# Portaqua.net
KiCad netlist of a schematic drawn in EAGLE
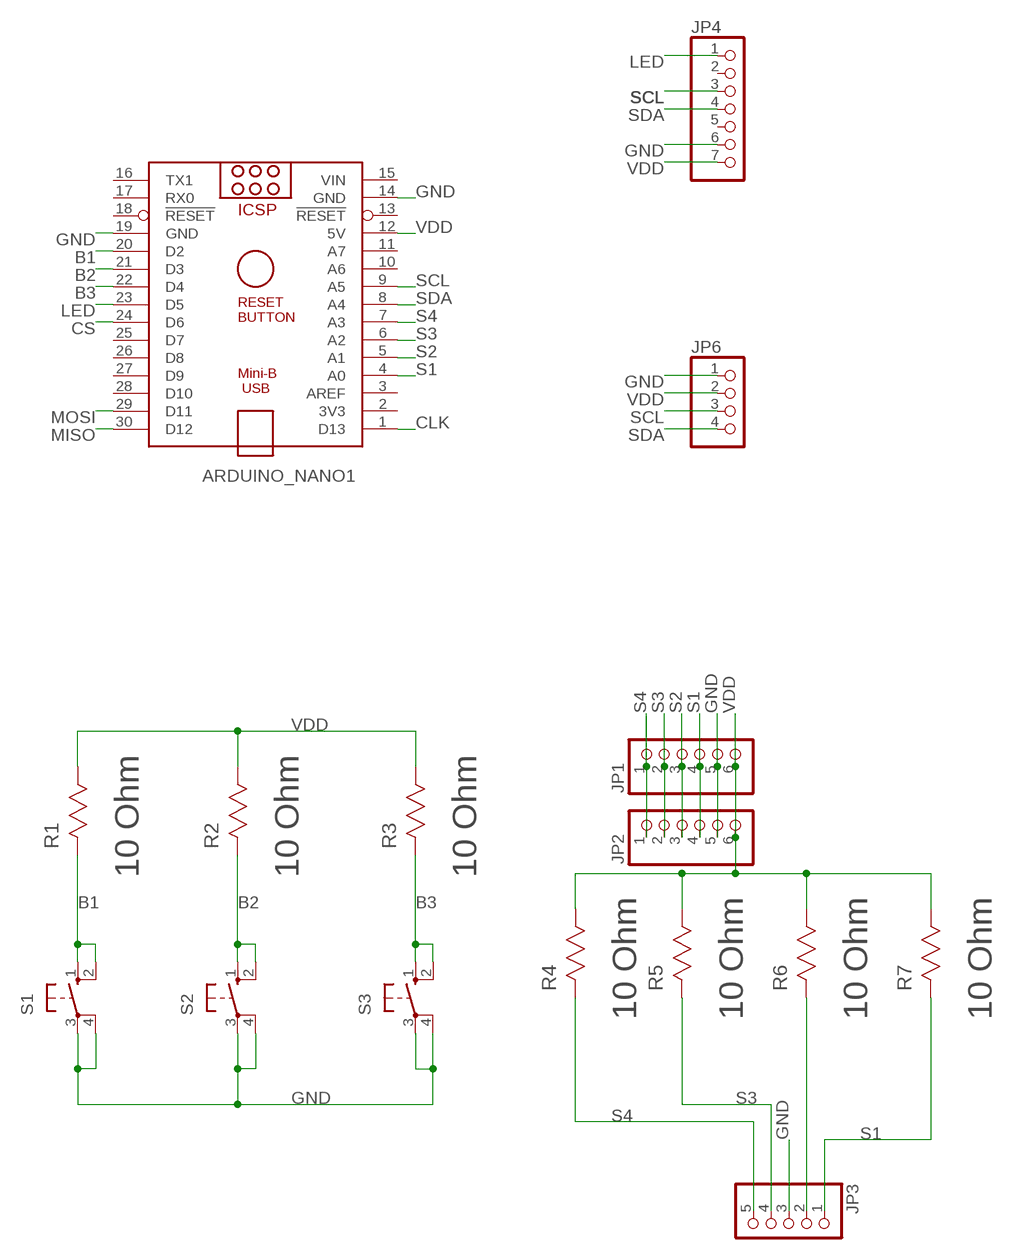
[diagram p0: schematic, sheet 1]

(export (version "E")
  (design (tool "Eeschema 10.0.6"))
  (components
    (comp (ref "ARDUINO_NANO1")
      (value "ARDUINO_NANO")
      (footprint "eagle-import:ARDUINO_NANO")
      (libsource (lib "eagle-import") (part "ARDUINO_NANO"))
    )
    (comp (ref "JP1")
      (value "PINHD-1X6")
      (footprint "eagle-import:1X06")
      (libsource (lib "eagle-import") (part "PINHD-1X6"))
    )
    (comp (ref "JP2")
      (value "PINHD-1X6")
      (footprint "eagle-import:1X06")
      (libsource (lib "eagle-import") (part "PINHD-1X6"))
    )
    (comp (ref "JP3")
      (value "PINHD-1X05_2.54-SMD-90°")
      (footprint "eagle-import:1X05SMD_90")
      (libsource (lib "eagle-import") (part "PINHD-1X05_2.54-SMD-90°"))
    )
    (comp (ref "JP4")
      (value "PINHD-1X7")
      (footprint "eagle-import:1X07")
      (libsource (lib "eagle-import") (part "PINHD-1X7"))
    )
    (comp (ref "JP6")
      (value "PINHD-1X4")
      (footprint "eagle-import:1X04")
      (libsource (lib "eagle-import") (part "PINHD-1X4"))
    )
    (comp (ref "R1")
      (value "10 Ohm")
      (footprint "eagle-import:RESC3216X71N")
      (fields (field (name "MPN") "CRM1206-FX-10R0ELF") (field (name "TOLERANCE") "±1 %"))
      (libsource (lib "eagle-import") (part "CRM1206-FX-10R0ELF"))
    )
    (comp (ref "R2")
      (value "10 Ohm")
      (footprint "eagle-import:RESC3216X71N")
      (fields (field (name "MPN") "CRM1206-FX-10R0ELF") (field (name "TOLERANCE") "±1 %"))
      (libsource (lib "eagle-import") (part "CRM1206-FX-10R0ELF"))
    )
    (comp (ref "R3")
      (value "10 Ohm")
      (footprint "eagle-import:RESC3216X71N")
      (fields (field (name "MPN") "CRM1206-FX-10R0ELF") (field (name "TOLERANCE") "±1 %"))
      (libsource (lib "eagle-import") (part "CRM1206-FX-10R0ELF"))
    )
    (comp (ref "R4")
      (value "10 Ohm")
      (footprint "eagle-import:RESC3216X71N")
      (fields (field (name "MPN") "CRM1206-FX-10R0ELF") (field (name "TOLERANCE") "±1 %"))
      (libsource (lib "eagle-import") (part "CRM1206-FX-10R0ELF"))
    )
    (comp (ref "R5")
      (value "10 Ohm")
      (footprint "eagle-import:RESC3216X71N")
      (fields (field (name "MPN") "CRM1206-FX-10R0ELF") (field (name "TOLERANCE") "±1 %"))
      (libsource (lib "eagle-import") (part "CRM1206-FX-10R0ELF"))
    )
    (comp (ref "R6")
      (value "10 Ohm")
      (footprint "eagle-import:RESC3216X71N")
      (fields (field (name "MPN") "CRM1206-FX-10R0ELF") (field (name "TOLERANCE") "±1 %"))
      (libsource (lib "eagle-import") (part "CRM1206-FX-10R0ELF"))
    )
    (comp (ref "R7")
      (value "10 Ohm")
      (footprint "eagle-import:RESC3216X71N")
      (fields (field (name "MPN") "CRM1206-FX-10R0ELF") (field (name "TOLERANCE") "±1 %"))
      (libsource (lib "eagle-import") (part "CRM1206-FX-10R0ELF"))
    )
    (comp (ref "S1")
      (value "10-XX")
      (footprint "eagle-import:B3F-10XX")
      (fields (field (name "MPN") "B3F-1000"))
      (libsource (lib "eagle-import") (part "10-XX"))
    )
    (comp (ref "S2")
      (value "10-XX")
      (footprint "eagle-import:B3F-10XX")
      (fields (field (name "MPN") "B3F-1000"))
      (libsource (lib "eagle-import") (part "10-XX"))
    )
    (comp (ref "S3")
      (value "10-XX")
      (footprint "eagle-import:B3F-10XX")
      (fields (field (name "MPN") "B3F-1000"))
      (libsource (lib "eagle-import") (part "10-XX"))
    )
  )
  (nets
    (net (code "1") (name "/B1") (class "Default")
      (node (ref "ARDUINO_NANO1") (pin "20") (pinfunction "D2_20") (pintype "bidirectional"))
      (node (ref "R1") (pin "2") (pinfunction "R2_2") (pintype "passive"))
      (node (ref "S1") (pin "1") (pinfunction "S_1") (pintype "passive"))
      (node (ref "S1") (pin "2") (pinfunction "S1_2") (pintype "passive"))
    )
    (net (code "2") (name "/B2") (class "Default")
      (node (ref "ARDUINO_NANO1") (pin "21") (pinfunction "D3_21") (pintype "bidirectional"))
      (node (ref "R2") (pin "2") (pinfunction "R2_2") (pintype "passive"))
      (node (ref "S2") (pin "1") (pinfunction "S_1") (pintype "passive"))
      (node (ref "S2") (pin "2") (pinfunction "S1_2") (pintype "passive"))
    )
    (net (code "3") (name "/B3") (class "Default")
      (node (ref "ARDUINO_NANO1") (pin "22") (pinfunction "D4_22") (pintype "bidirectional"))
      (node (ref "R3") (pin "2") (pinfunction "R2_2") (pintype "passive"))
      (node (ref "S3") (pin "1") (pinfunction "S_1") (pintype "passive"))
      (node (ref "S3") (pin "2") (pinfunction "S1_2") (pintype "passive"))
    )
    (net (code "4") (name "/CLK") (class "Default")
      (node (ref "ARDUINO_NANO1") (pin "1") (pinfunction "D13_1") (pintype "bidirectional"))
    )
    (net (code "5") (name "/CS") (class "Default")
      (node (ref "ARDUINO_NANO1") (pin "24") (pinfunction "D6_24") (pintype "bidirectional"))
    )
    (net (code "6") (name "/GND") (class "Default")
      (node (ref "ARDUINO_NANO1") (pin "14") (pinfunction "GND_14") (pintype "power_in"))
      (node (ref "ARDUINO_NANO1") (pin "19") (pinfunction "GND_19") (pintype "power_in"))
      (node (ref "JP1") (pin "5") (pinfunction "5_5") (pintype "passive"))
      (node (ref "JP2") (pin "5") (pinfunction "5_5") (pintype "passive"))
      (node (ref "JP3") (pin "3") (pinfunction "3_3") (pintype "passive"))
      (node (ref "JP4") (pin "6") (pinfunction "6_6") (pintype "passive"))
      (node (ref "JP6") (pin "1") (pinfunction "1_1") (pintype "passive"))
      (node (ref "S1") (pin "3") (pinfunction "P_3") (pintype "passive"))
      (node (ref "S1") (pin "4") (pinfunction "P1_4") (pintype "passive"))
      (node (ref "S2") (pin "3") (pinfunction "P_3") (pintype "passive"))
      (node (ref "S2") (pin "4") (pinfunction "P1_4") (pintype "passive"))
      (node (ref "S3") (pin "3") (pinfunction "P_3") (pintype "passive"))
      (node (ref "S3") (pin "4") (pinfunction "P1_4") (pintype "passive"))
    )
    (net (code "7") (name "/LED") (class "Default")
      (node (ref "ARDUINO_NANO1") (pin "23") (pinfunction "D5_23") (pintype "bidirectional"))
      (node (ref "JP4") (pin "1") (pinfunction "1_1") (pintype "passive"))
    )
    (net (code "8") (name "/MISO") (class "Default")
      (node (ref "ARDUINO_NANO1") (pin "30") (pinfunction "D12_30") (pintype "bidirectional"))
    )
    (net (code "9") (name "/MOSI") (class "Default")
      (node (ref "ARDUINO_NANO1") (pin "29") (pinfunction "D11_29") (pintype "bidirectional"))
    )
    (net (code "10") (name "/S1") (class "Default")
      (node (ref "ARDUINO_NANO1") (pin "4") (pinfunction "A0_4") (pintype "bidirectional"))
      (node (ref "JP1") (pin "4") (pinfunction "4_4") (pintype "passive"))
      (node (ref "JP2") (pin "4") (pinfunction "4_4") (pintype "passive"))
      (node (ref "JP3") (pin "1") (pinfunction "1_1") (pintype "passive"))
      (node (ref "R7") (pin "2") (pinfunction "R2_2") (pintype "passive"))
    )
    (net (code "11") (name "/S2") (class "Default")
      (node (ref "ARDUINO_NANO1") (pin "5") (pinfunction "A1_5") (pintype "bidirectional"))
      (node (ref "JP1") (pin "3") (pinfunction "3_3") (pintype "passive"))
      (node (ref "JP2") (pin "3") (pinfunction "3_3") (pintype "passive"))
    )
    (net (code "12") (name "/S3") (class "Default")
      (node (ref "ARDUINO_NANO1") (pin "6") (pinfunction "A2_6") (pintype "bidirectional"))
      (node (ref "JP1") (pin "2") (pinfunction "2_2") (pintype "passive"))
      (node (ref "JP2") (pin "2") (pinfunction "2_2") (pintype "passive"))
      (node (ref "JP3") (pin "4") (pinfunction "4_4") (pintype "passive"))
      (node (ref "R5") (pin "2") (pinfunction "R2_2") (pintype "passive"))
    )
    (net (code "13") (name "/S4") (class "Default")
      (node (ref "ARDUINO_NANO1") (pin "7") (pinfunction "A3_7") (pintype "bidirectional"))
      (node (ref "JP1") (pin "1") (pinfunction "1_1") (pintype "passive"))
      (node (ref "JP2") (pin "1") (pinfunction "1_1") (pintype "passive"))
      (node (ref "JP3") (pin "5") (pinfunction "5_5") (pintype "passive"))
      (node (ref "R4") (pin "2") (pinfunction "R2_2") (pintype "passive"))
    )
    (net (code "14") (name "/SCL") (class "Default")
      (node (ref "ARDUINO_NANO1") (pin "9") (pinfunction "A5_9") (pintype "bidirectional"))
      (node (ref "JP4") (pin "3") (pinfunction "3_3") (pintype "passive"))
      (node (ref "JP6") (pin "3") (pinfunction "3_3") (pintype "passive"))
    )
    (net (code "15") (name "/SDA") (class "Default")
      (node (ref "ARDUINO_NANO1") (pin "8") (pinfunction "A4_8") (pintype "bidirectional"))
      (node (ref "JP4") (pin "4") (pinfunction "4_4") (pintype "passive"))
      (node (ref "JP6") (pin "4") (pinfunction "4_4") (pintype "passive"))
    )
    (net (code "16") (name "/VDD") (class "Default")
      (node (ref "ARDUINO_NANO1") (pin "12") (pinfunction "5V_12") (pintype "power_in"))
      (node (ref "JP1") (pin "6") (pinfunction "6_6") (pintype "passive"))
      (node (ref "JP2") (pin "6") (pinfunction "6_6") (pintype "passive"))
      (node (ref "JP4") (pin "7") (pinfunction "7_7") (pintype "passive"))
      (node (ref "JP6") (pin "2") (pinfunction "2_2") (pintype "passive"))
      (node (ref "R1") (pin "1") (pinfunction "R1_1") (pintype "passive"))
      (node (ref "R2") (pin "1") (pinfunction "R1_1") (pintype "passive"))
      (node (ref "R3") (pin "1") (pinfunction "R1_1") (pintype "passive"))
      (node (ref "R4") (pin "1") (pinfunction "R1_1") (pintype "passive"))
      (node (ref "R5") (pin "1") (pinfunction "R1_1") (pintype "passive"))
      (node (ref "R6") (pin "1") (pinfunction "R1_1") (pintype "passive"))
      (node (ref "R7") (pin "1") (pinfunction "R1_1") (pintype "passive"))
    )
    (net (code "17") (name "/VIN") (class "Default")
      (node (ref "ARDUINO_NANO1") (pin "15") (pinfunction "VIN_15") (pintype "power_in"))
    )
    (net (code "18") (name "Net-(R6-R2)") (class "Default")
      (node (ref "JP3") (pin "2") (pinfunction "2_2") (pintype "passive"))
      (node (ref "R6") (pin "2") (pinfunction "R2_2") (pintype "passive"))
    )
    (net (code "19") (name "unconnected-(ARDUINO_NANO1-3V3-Pad2)") (class "Default")
      (node (ref "ARDUINO_NANO1") (pin "2") (pinfunction "3V3_2") (pintype "output"))
    )
    (net (code "20") (name "unconnected-(ARDUINO_NANO1-A6-Pad10)") (class "Default")
      (node (ref "ARDUINO_NANO1") (pin "10") (pinfunction "A6_10") (pintype "bidirectional"))
    )
    (net (code "21") (name "unconnected-(ARDUINO_NANO1-A7-Pad11)") (class "Default")
      (node (ref "ARDUINO_NANO1") (pin "11") (pinfunction "A7_11") (pintype "bidirectional"))
    )
    (net (code "22") (name "unconnected-(ARDUINO_NANO1-AREF-Pad3)") (class "Default")
      (node (ref "ARDUINO_NANO1") (pin "3") (pinfunction "AREF_3") (pintype "input"))
    )
    (net (code "23") (name "unconnected-(ARDUINO_NANO1-D7-Pad25)") (class "Default")
      (node (ref "ARDUINO_NANO1") (pin "25") (pinfunction "D7_25") (pintype "bidirectional"))
    )
    (net (code "24") (name "unconnected-(ARDUINO_NANO1-D8-Pad26)") (class "Default")
      (node (ref "ARDUINO_NANO1") (pin "26") (pinfunction "D8_26") (pintype "bidirectional"))
    )
    (net (code "25") (name "unconnected-(ARDUINO_NANO1-D9-Pad27)") (class "Default")
      (node (ref "ARDUINO_NANO1") (pin "27") (pinfunction "D9_27") (pintype "bidirectional"))
    )
    (net (code "26") (name "unconnected-(ARDUINO_NANO1-D10-Pad28)") (class "Default")
      (node (ref "ARDUINO_NANO1") (pin "28") (pinfunction "D10_28") (pintype "bidirectional"))
    )
    (net (code "27") (name "unconnected-(ARDUINO_NANO1-RX0-Pad17)") (class "Default")
      (node (ref "ARDUINO_NANO1") (pin "17") (pinfunction "RX0_17") (pintype "bidirectional"))
    )
    (net (code "28") (name "unconnected-(ARDUINO_NANO1-TX1-Pad16)") (class "Default")
      (node (ref "ARDUINO_NANO1") (pin "16") (pinfunction "TX1_16") (pintype "bidirectional"))
    )
    (net (code "29") (name "unconnected-(ARDUINO_NANO1-~{RESET}-Pad13)") (class "Default")
      (node (ref "ARDUINO_NANO1") (pin "13") (pinfunction "~{RESET}_13") (pintype "input"))
    )
    (net (code "30") (name "unconnected-(ARDUINO_NANO1-~{RESET}-Pad18)") (class "Default")
      (node (ref "ARDUINO_NANO1") (pin "18") (pinfunction "~{RESET}_18") (pintype "input"))
    )
    (net (code "31") (name "unconnected-(JP4-Pad2)") (class "Default")
      (node (ref "JP4") (pin "2") (pinfunction "2_2") (pintype "passive"))
    )
    (net (code "32") (name "unconnected-(JP4-Pad5)") (class "Default")
      (node (ref "JP4") (pin "5") (pinfunction "5_5") (pintype "passive"))
    )
  )
)
